# RGBNDR.net
KiCad netlist of a schematic drawn in EAGLE
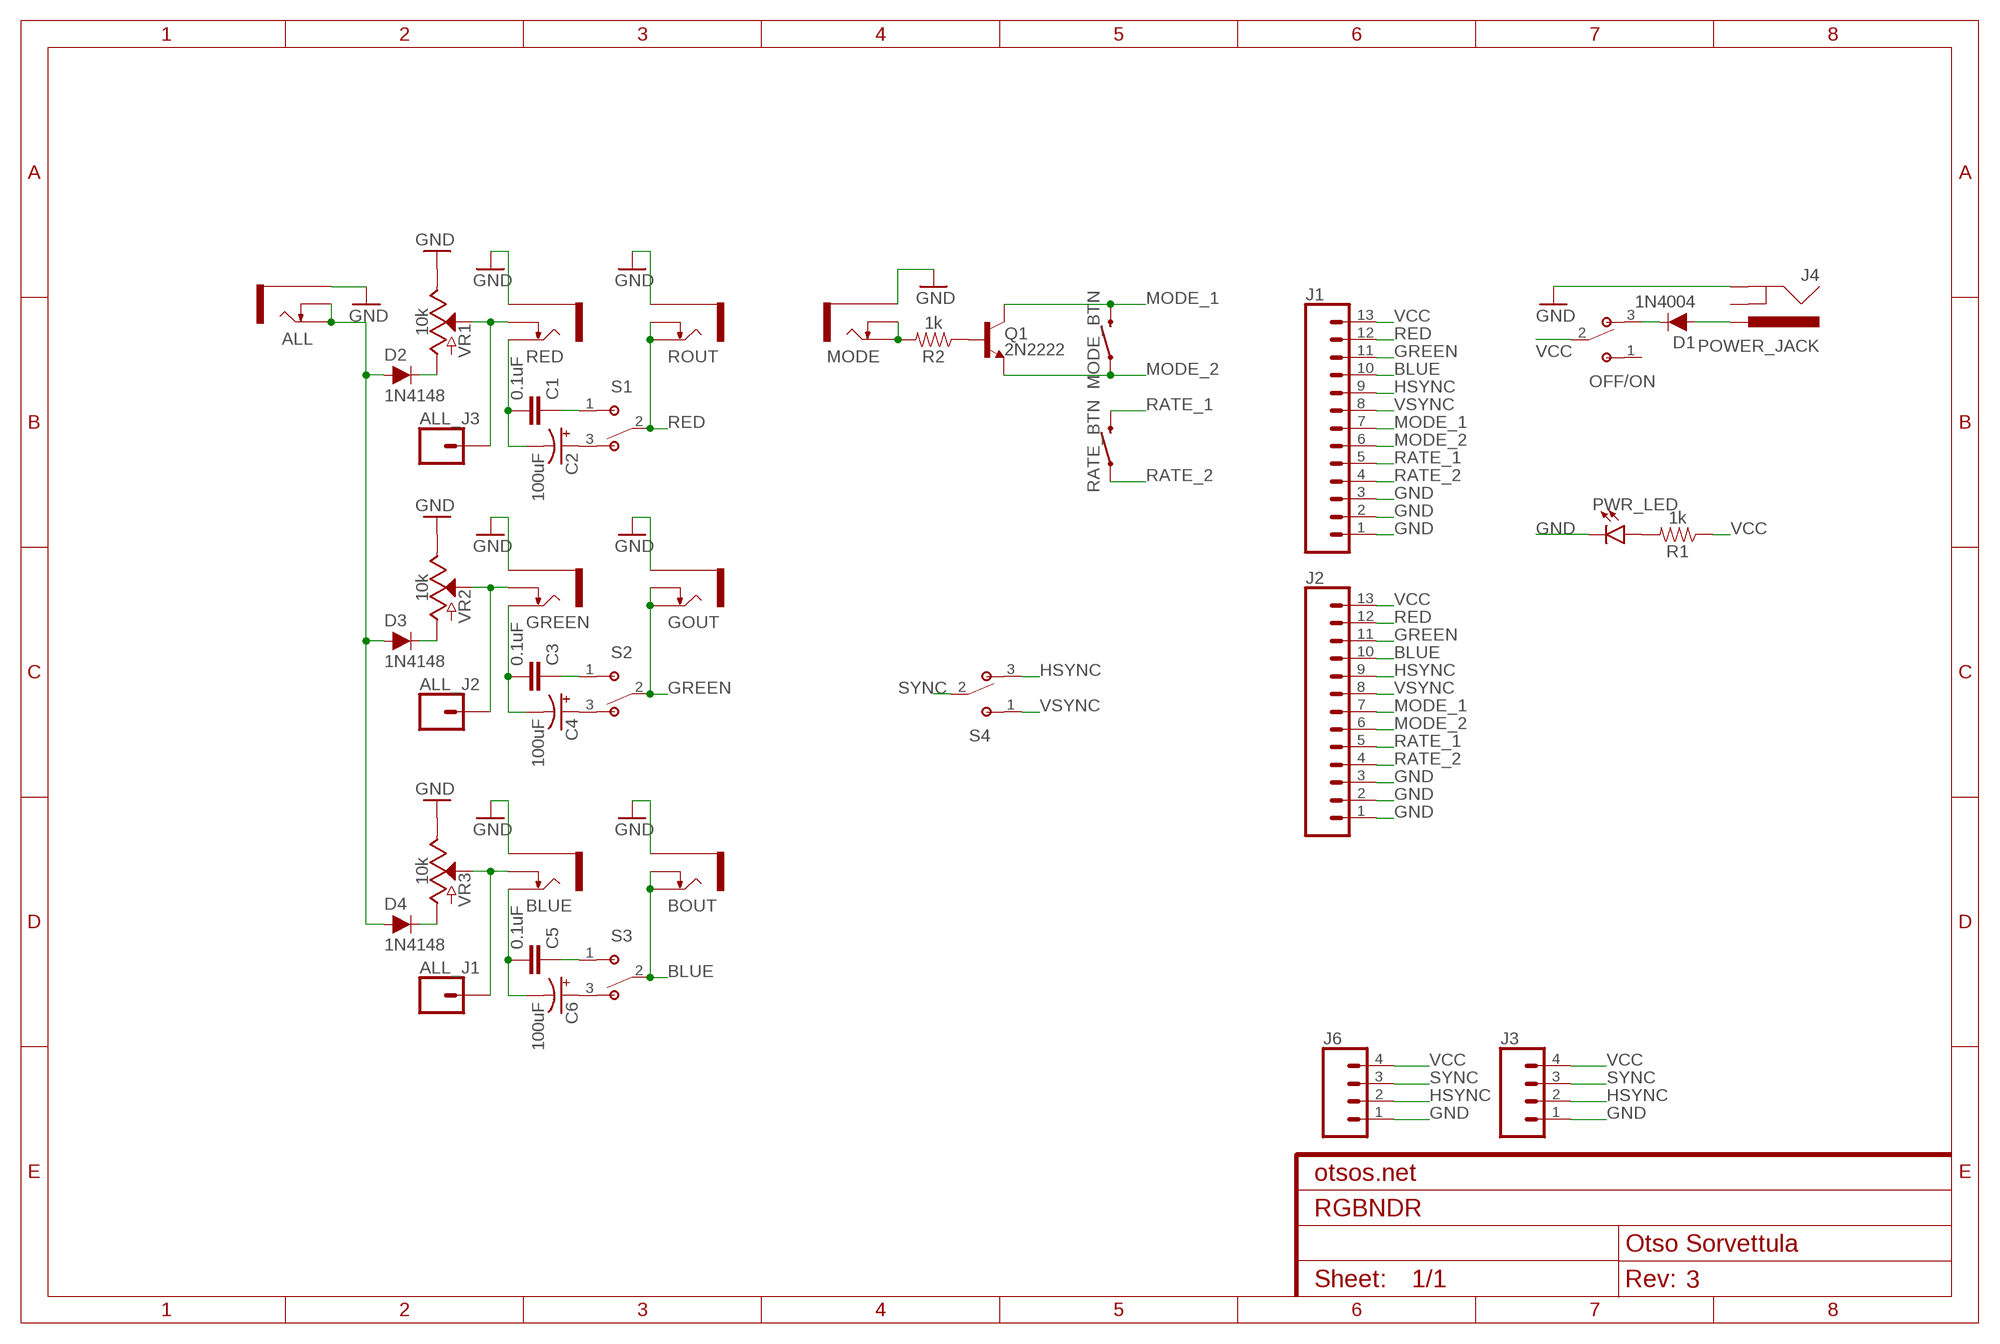
[diagram p0: schematic, sheet 1]

(export (version "E")
  (design (tool "Eeschema 10.0.6"))
  (components
    (comp (ref "ALL")
      (value "THONKICONNNEW")
      (footprint "eagle-import:WQP-PJ301M-12_JACK")
      (libsource (lib "eagle-import") (part "THONKICONNNEW"))
    )
    (comp (ref "ALL_J1")
      (value "CONN_01PTH_NO_SILK_YES_STOP")
      (footprint "eagle-import:1X01_NO_SILK")
      (libsource (lib "eagle-import") (part "CONN_01PTH_NO_SILK_YES_STOP"))
    )
    (comp (ref "ALL_J2")
      (value "CONN_01PTH_NO_SILK_YES_STOP")
      (footprint "eagle-import:1X01_NO_SILK")
      (libsource (lib "eagle-import") (part "CONN_01PTH_NO_SILK_YES_STOP"))
    )
    (comp (ref "ALL_J3")
      (value "CONN_01PTH_NO_SILK_YES_STOP")
      (footprint "eagle-import:1X01_NO_SILK")
      (libsource (lib "eagle-import") (part "CONN_01PTH_NO_SILK_YES_STOP"))
    )
    (comp (ref "BLUE")
      (value "THONKICONNNEW")
      (footprint "eagle-import:WQP-PJ301M-12_JACK")
      (libsource (lib "eagle-import") (part "THONKICONNNEW"))
    )
    (comp (ref "BOUT")
      (value "THONKICONNNEW")
      (footprint "eagle-import:WQP-PJ301M-12_JACK")
      (libsource (lib "eagle-import") (part "THONKICONNNEW"))
    )
    (comp (ref "C1")
      (value "0.1uF")
      (footprint "eagle-import:C025-025X050")
      (libsource (lib "eagle-import") (part "C-EU025-025X050"))
    )
    (comp (ref "C2")
      (value "100uF")
      (footprint "eagle-import:CPOL-RADIAL-2.5MM-6.5MM")
      (libsource (lib "eagle-import") (part "100UF-POLAR-RADIAL-2.5MM-25V-20%"))
    )
    (comp (ref "C3")
      (value "0.1uF")
      (footprint "eagle-import:C025-025X050")
      (libsource (lib "eagle-import") (part "C-EU025-025X050"))
    )
    (comp (ref "C4")
      (value "100uF")
      (footprint "eagle-import:CPOL-RADIAL-2.5MM-6.5MM")
      (libsource (lib "eagle-import") (part "100UF-POLAR-RADIAL-2.5MM-25V-20%"))
    )
    (comp (ref "C5")
      (value "0.1uF")
      (footprint "eagle-import:C025-025X050")
      (libsource (lib "eagle-import") (part "C-EU025-025X050"))
    )
    (comp (ref "C6")
      (value "100uF")
      (footprint "eagle-import:CPOL-RADIAL-2.5MM-6.5MM")
      (libsource (lib "eagle-import") (part "100UF-POLAR-RADIAL-2.5MM-25V-20%"))
    )
    (comp (ref "D1")
      (value "1N4004")
      (footprint "eagle-import:DIODE-1N4001")
      (libsource (lib "eagle-import") (part "DIODE-PTH"))
    )
    (comp (ref "D2")
      (value "1N4148")
      (footprint "eagle-import:DIODE-1N4148")
      (libsource (lib "eagle-import") (part "DIODE-1N4148"))
    )
    (comp (ref "D3")
      (value "1N4148")
      (footprint "eagle-import:DIODE-1N4148")
      (libsource (lib "eagle-import") (part "DIODE-1N4148"))
    )
    (comp (ref "D4")
      (value "1N4148")
      (footprint "eagle-import:DIODE-1N4148")
      (libsource (lib "eagle-import") (part "DIODE-1N4148"))
    )
    (comp (ref "GOUT")
      (value "THONKICONNNEW")
      (footprint "eagle-import:WQP-PJ301M-12_JACK")
      (libsource (lib "eagle-import") (part "THONKICONNNEW"))
    )
    (comp (ref "GREEN")
      (value "THONKICONNNEW")
      (footprint "eagle-import:WQP-PJ301M-12_JACK")
      (libsource (lib "eagle-import") (part "THONKICONNNEW"))
    )
    (comp (ref "J1")
      (value "CONN_13LONGPADS")
      (footprint "eagle-import:1X13-LONGPADS")
      (libsource (lib "eagle-import") (part "CONN_13LONGPADS"))
    )
    (comp (ref "J2")
      (value "CONN_13LONGPADS")
      (footprint "eagle-import:1X13-LONGPADS")
      (libsource (lib "eagle-import") (part "CONN_13LONGPADS"))
    )
    (comp (ref "J3")
      (value "CONN_04")
      (footprint "eagle-import:1X04")
      (libsource (lib "eagle-import") (part "CONN_04"))
    )
    (comp (ref "J4")
      (value "POWER_JACK")
      (footprint "eagle-import:POWER_JACK_PTH")
      (libsource (lib "eagle-import") (part "POWER_JACK"))
    )
    (comp (ref "J6")
      (value "CONN_04")
      (footprint "eagle-import:1X04")
      (libsource (lib "eagle-import") (part "CONN_04"))
    )
    (comp (ref "MODE")
      (value "THONKICONNNEW")
      (footprint "eagle-import:WQP-PJ301M-12_JACK")
      (libsource (lib "eagle-import") (part "THONKICONNNEW"))
    )
    (comp (ref "MODE_BTN")
      (value "MOMENTARY-SWITCH-SPST-PTH-6.0MM")
      (footprint "eagle-import:TACTILE_SWITCH_PTH_6.0MM")
      (libsource (lib "eagle-import") (part "MOMENTARY-SWITCH-SPST-PTH-6.0MM"))
    )
    (comp (ref "OFF/ON")
      (value "OS102011MS2QN1")
      (footprint "eagle-import:SW_OS102011MS2QN1")
      (fields (field (name "MF") "C&K"))
      (libsource (lib "eagle-import") (part "OS102011MS2QN1"))
    )
    (comp (ref "PWR_LED")
      (value "LED3MM")
      (footprint "eagle-import:LED_3MM")
      (libsource (lib "eagle-import") (part "LED3MM"))
    )
    (comp (ref "Q1")
      (value "2N2222")
      (footprint "eagle-import:TO-92")
      (libsource (lib "eagle-import") (part "TRANS_NPN-2N3904"))
    )
    (comp (ref "R1")
      (value "1k")
      (footprint "eagle-import:AXIAL-0.3")
      (libsource (lib "eagle-import") (part "1KOHM-HORIZ-1/4W-1%"))
    )
    (comp (ref "R2")
      (value "1k")
      (footprint "eagle-import:AXIAL-0.3")
      (libsource (lib "eagle-import") (part "1KOHM-HORIZ-1/4W-1%"))
    )
    (comp (ref "RATE_BTN")
      (value "MOMENTARY-SWITCH-SPST-PTH-6.0MM")
      (footprint "eagle-import:TACTILE_SWITCH_PTH_6.0MM")
      (libsource (lib "eagle-import") (part "MOMENTARY-SWITCH-SPST-PTH-6.0MM"))
    )
    (comp (ref "RED")
      (value "THONKICONNNEW")
      (footprint "eagle-import:WQP-PJ301M-12_JACK")
      (libsource (lib "eagle-import") (part "THONKICONNNEW"))
    )
    (comp (ref "ROUT")
      (value "THONKICONNNEW")
      (footprint "eagle-import:WQP-PJ301M-12_JACK")
      (libsource (lib "eagle-import") (part "THONKICONNNEW"))
    )
    (comp (ref "S1")
      (value "OS102011MS2QN1")
      (footprint "eagle-import:SW_OS102011MS2QN1")
      (fields (field (name "MF") "C&K"))
      (libsource (lib "eagle-import") (part "OS102011MS2QN1"))
    )
    (comp (ref "S2")
      (value "OS102011MS2QN1")
      (footprint "eagle-import:SW_OS102011MS2QN1")
      (fields (field (name "MF") "C&K"))
      (libsource (lib "eagle-import") (part "OS102011MS2QN1"))
    )
    (comp (ref "S3")
      (value "OS102011MS2QN1")
      (footprint "eagle-import:SW_OS102011MS2QN1")
      (fields (field (name "MF") "C&K"))
      (libsource (lib "eagle-import") (part "OS102011MS2QN1"))
    )
    (comp (ref "S4")
      (value "OS102011MS2QN1")
      (footprint "eagle-import:SW_OS102011MS2QN1")
      (fields (field (name "MF") "C&K"))
      (libsource (lib "eagle-import") (part "OS102011MS2QN1"))
    )
    (comp (ref "VR1")
      (value "10k")
      (footprint "eagle-import:POT-PTH-ALPS")
      (libsource (lib "eagle-import") (part "POTENTIOMETER-PTH-9MM-1/20W-20%"))
    )
    (comp (ref "VR2")
      (value "10k")
      (footprint "eagle-import:POT-PTH-ALPS")
      (libsource (lib "eagle-import") (part "POTENTIOMETER-PTH-9MM-1/20W-20%"))
    )
    (comp (ref "VR3")
      (value "10k")
      (footprint "eagle-import:POT-PTH-ALPS")
      (libsource (lib "eagle-import") (part "POTENTIOMETER-PTH-9MM-1/20W-20%"))
    )
  )
  (nets
    (net (code "1") (name "/BLUE") (class "Default")
      (node (ref "BOUT") (pin "P$1_TIP") (pinfunction "TIP_P$1_TIP") (pintype "passive"))
      (node (ref "BOUT") (pin "P$2_SWITCH") (pinfunction "SWITCH_P$2_SWITCH") (pintype "passive"))
      (node (ref "J1") (pin "10") (pinfunction "10_10") (pintype "passive"))
      (node (ref "J2") (pin "10") (pinfunction "10_10") (pintype "passive"))
      (node (ref "S3") (pin "2") (pinfunction "2_2") (pintype "passive"))
    )
    (net (code "2") (name "/GREEN") (class "Default")
      (node (ref "GOUT") (pin "P$1_TIP") (pinfunction "TIP_P$1_TIP") (pintype "passive"))
      (node (ref "GOUT") (pin "P$2_SWITCH") (pinfunction "SWITCH_P$2_SWITCH") (pintype "passive"))
      (node (ref "J1") (pin "11") (pinfunction "11_11") (pintype "passive"))
      (node (ref "J2") (pin "11") (pinfunction "11_11") (pintype "passive"))
      (node (ref "S2") (pin "2") (pinfunction "2_2") (pintype "passive"))
    )
    (net (code "3") (name "/HSYNC") (class "Default")
      (node (ref "J1") (pin "9") (pinfunction "9_9") (pintype "passive"))
      (node (ref "J2") (pin "9") (pinfunction "9_9") (pintype "passive"))
      (node (ref "J3") (pin "2") (pinfunction "2_2") (pintype "passive"))
      (node (ref "J6") (pin "2") (pinfunction "2_2") (pintype "passive"))
      (node (ref "S4") (pin "3") (pinfunction "3_3") (pintype "passive"))
    )
    (net (code "4") (name "/MODE_1") (class "Default")
      (node (ref "J1") (pin "7") (pinfunction "7_7") (pintype "passive"))
      (node (ref "J2") (pin "7") (pinfunction "7_7") (pintype "passive"))
      (node (ref "MODE_BTN") (pin "3") (pinfunction "2_3") (pintype "passive"))
      (node (ref "Q1") (pin "3") (pinfunction "C_3") (pintype "passive"))
    )
    (net (code "5") (name "/MODE_2") (class "Default")
      (node (ref "J1") (pin "6") (pinfunction "6_6") (pintype "passive"))
      (node (ref "J2") (pin "6") (pinfunction "6_6") (pintype "passive"))
      (node (ref "MODE_BTN") (pin "1") (pinfunction "1_1") (pintype "passive"))
      (node (ref "Q1") (pin "1") (pinfunction "E_1") (pintype "passive"))
    )
    (net (code "6") (name "/RATE_1") (class "Default")
      (node (ref "J1") (pin "5") (pinfunction "5_5") (pintype "passive"))
      (node (ref "J2") (pin "5") (pinfunction "5_5") (pintype "passive"))
      (node (ref "RATE_BTN") (pin "3") (pinfunction "2_3") (pintype "passive"))
    )
    (net (code "7") (name "/RATE_2") (class "Default")
      (node (ref "J1") (pin "4") (pinfunction "4_4") (pintype "passive"))
      (node (ref "J2") (pin "4") (pinfunction "4_4") (pintype "passive"))
      (node (ref "RATE_BTN") (pin "1") (pinfunction "1_1") (pintype "passive"))
    )
    (net (code "8") (name "/RED") (class "Default")
      (node (ref "J1") (pin "12") (pinfunction "12_12") (pintype "passive"))
      (node (ref "J2") (pin "12") (pinfunction "12_12") (pintype "passive"))
      (node (ref "ROUT") (pin "P$1_TIP") (pinfunction "TIP_P$1_TIP") (pintype "passive"))
      (node (ref "ROUT") (pin "P$2_SWITCH") (pinfunction "SWITCH_P$2_SWITCH") (pintype "passive"))
      (node (ref "S1") (pin "2") (pinfunction "2_2") (pintype "passive"))
    )
    (net (code "9") (name "/SYNC") (class "Default")
      (node (ref "J3") (pin "3") (pinfunction "3_3") (pintype "passive"))
      (node (ref "J6") (pin "3") (pinfunction "3_3") (pintype "passive"))
      (node (ref "S4") (pin "2") (pinfunction "2_2") (pintype "passive"))
    )
    (net (code "10") (name "/VCC") (class "Default")
      (node (ref "J1") (pin "13") (pinfunction "13_13") (pintype "passive"))
      (node (ref "J2") (pin "13") (pinfunction "13_13") (pintype "passive"))
      (node (ref "J3") (pin "4") (pinfunction "4_4") (pintype "passive"))
      (node (ref "J6") (pin "4") (pinfunction "4_4") (pintype "passive"))
      (node (ref "OFF/ON") (pin "2") (pinfunction "2_2") (pintype "passive"))
      (node (ref "R1") (pin "P$1") (pinfunction "1_P$1") (pintype "passive"))
    )
    (net (code "11") (name "/VSYNC") (class "Default")
      (node (ref "J1") (pin "8") (pinfunction "8_8") (pintype "passive"))
      (node (ref "J2") (pin "8") (pinfunction "8_8") (pintype "passive"))
      (node (ref "S4") (pin "1") (pinfunction "1_1") (pintype "passive"))
    )
    (net (code "12") (name "GND") (class "Default")
      (node (ref "ALL") (pin "P$3_SLEEVE") (pinfunction "SLEEVE_P$3_SLEEVE") (pintype "passive"))
      (node (ref "BLUE") (pin "P$3_SLEEVE") (pinfunction "SLEEVE_P$3_SLEEVE") (pintype "passive"))
      (node (ref "BOUT") (pin "P$3_SLEEVE") (pinfunction "SLEEVE_P$3_SLEEVE") (pintype "passive"))
      (node (ref "GOUT") (pin "P$3_SLEEVE") (pinfunction "SLEEVE_P$3_SLEEVE") (pintype "passive"))
      (node (ref "GREEN") (pin "P$3_SLEEVE") (pinfunction "SLEEVE_P$3_SLEEVE") (pintype "passive"))
      (node (ref "J1") (pin "1") (pinfunction "1_1") (pintype "passive"))
      (node (ref "J1") (pin "2") (pinfunction "2_2") (pintype "passive"))
      (node (ref "J1") (pin "3") (pinfunction "3_3") (pintype "passive"))
      (node (ref "J2") (pin "1") (pinfunction "1_1") (pintype "passive"))
      (node (ref "J2") (pin "2") (pinfunction "2_2") (pintype "passive"))
      (node (ref "J2") (pin "3") (pinfunction "3_3") (pintype "passive"))
      (node (ref "J3") (pin "1") (pinfunction "1_1") (pintype "passive"))
      (node (ref "J4") (pin "GND") (pinfunction "GND_GND") (pintype "bidirectional"))
      (node (ref "J6") (pin "1") (pinfunction "1_1") (pintype "passive"))
      (node (ref "MODE") (pin "P$3_SLEEVE") (pinfunction "SLEEVE_P$3_SLEEVE") (pintype "passive"))
      (node (ref "PWR_LED") (pin "K") (pinfunction "C_K") (pintype "passive"))
      (node (ref "RED") (pin "P$3_SLEEVE") (pinfunction "SLEEVE_P$3_SLEEVE") (pintype "passive"))
      (node (ref "ROUT") (pin "P$3_SLEEVE") (pinfunction "SLEEVE_P$3_SLEEVE") (pintype "passive"))
      (node (ref "VR1") (pin "P$1") (pinfunction "E_P$1") (pintype "passive"))
      (node (ref "VR2") (pin "P$1") (pinfunction "E_P$1") (pintype "passive"))
      (node (ref "VR3") (pin "P$1") (pinfunction "E_P$1") (pintype "passive"))
    )
    (net (code "13") (name "Net-(ALL-SWITCH)") (class "Default")
      (node (ref "ALL") (pin "P$1_TIP") (pinfunction "TIP_P$1_TIP") (pintype "passive"))
      (node (ref "ALL") (pin "P$2_SWITCH") (pinfunction "SWITCH_P$2_SWITCH") (pintype "passive"))
      (node (ref "D2") (pin "A") (pinfunction "A_A") (pintype "passive"))
      (node (ref "D3") (pin "A") (pinfunction "A_A") (pintype "passive"))
      (node (ref "D4") (pin "A") (pinfunction "A_A") (pintype "passive"))
    )
    (net (code "14") (name "Net-(BLUE-SWITCH)") (class "Default")
      (node (ref "ALL_J1") (pin "1") (pinfunction "1_1") (pintype "passive"))
      (node (ref "BLUE") (pin "P$2_SWITCH") (pinfunction "SWITCH_P$2_SWITCH") (pintype "passive"))
      (node (ref "VR3") (pin "P$2") (pinfunction "S_P$2") (pintype "passive"))
    )
    (net (code "15") (name "Net-(BLUE-TIP)") (class "Default")
      (node (ref "BLUE") (pin "P$1_TIP") (pinfunction "TIP_P$1_TIP") (pintype "passive"))
      (node (ref "C5") (pin "2") (pinfunction "2_2") (pintype "passive"))
      (node (ref "C6") (pin "2") (pinfunction "-_2") (pintype "passive"))
    )
    (net (code "16") (name "Net-(C1-Pad1)") (class "Default")
      (node (ref "C1") (pin "1") (pinfunction "1_1") (pintype "passive"))
      (node (ref "S1") (pin "1") (pinfunction "1_1") (pintype "passive"))
    )
    (net (code "17") (name "Net-(C2-+)") (class "Default")
      (node (ref "C2") (pin "1") (pinfunction "+_1") (pintype "passive"))
      (node (ref "S1") (pin "3") (pinfunction "3_3") (pintype "passive"))
    )
    (net (code "18") (name "Net-(C2--)") (class "Default")
      (node (ref "C1") (pin "2") (pinfunction "2_2") (pintype "passive"))
      (node (ref "C2") (pin "2") (pinfunction "-_2") (pintype "passive"))
      (node (ref "RED") (pin "P$1_TIP") (pinfunction "TIP_P$1_TIP") (pintype "passive"))
    )
    (net (code "19") (name "Net-(C3-Pad1)") (class "Default")
      (node (ref "C3") (pin "1") (pinfunction "1_1") (pintype "passive"))
      (node (ref "S2") (pin "1") (pinfunction "1_1") (pintype "passive"))
    )
    (net (code "20") (name "Net-(C4-+)") (class "Default")
      (node (ref "C4") (pin "1") (pinfunction "+_1") (pintype "passive"))
      (node (ref "S2") (pin "3") (pinfunction "3_3") (pintype "passive"))
    )
    (net (code "21") (name "Net-(C4--)") (class "Default")
      (node (ref "C3") (pin "2") (pinfunction "2_2") (pintype "passive"))
      (node (ref "C4") (pin "2") (pinfunction "-_2") (pintype "passive"))
      (node (ref "GREEN") (pin "P$1_TIP") (pinfunction "TIP_P$1_TIP") (pintype "passive"))
    )
    (net (code "22") (name "Net-(C5-Pad1)") (class "Default")
      (node (ref "C5") (pin "1") (pinfunction "1_1") (pintype "passive"))
      (node (ref "S3") (pin "1") (pinfunction "1_1") (pintype "passive"))
    )
    (net (code "23") (name "Net-(C6-+)") (class "Default")
      (node (ref "C6") (pin "1") (pinfunction "+_1") (pintype "passive"))
      (node (ref "S3") (pin "3") (pinfunction "3_3") (pintype "passive"))
    )
    (net (code "24") (name "Net-(D1-PadA)") (class "Default")
      (node (ref "D1") (pin "A") (pinfunction "A_A") (pintype "passive"))
      (node (ref "J4") (pin "PWR") (pinfunction "PWR_PWR") (pintype "bidirectional"))
    )
    (net (code "25") (name "Net-(D1-PadC)") (class "Default")
      (node (ref "D1") (pin "C") (pinfunction "C_C") (pintype "passive"))
      (node (ref "OFF/ON") (pin "3") (pinfunction "3_3") (pintype "passive"))
    )
    (net (code "26") (name "Net-(GREEN-SWITCH)") (class "Default")
      (node (ref "ALL_J2") (pin "1") (pinfunction "1_1") (pintype "passive"))
      (node (ref "GREEN") (pin "P$2_SWITCH") (pinfunction "SWITCH_P$2_SWITCH") (pintype "passive"))
      (node (ref "VR2") (pin "P$2") (pinfunction "S_P$2") (pintype "passive"))
    )
    (net (code "27") (name "Net-(MODE-SWITCH)") (class "Default")
      (node (ref "MODE") (pin "P$1_TIP") (pinfunction "TIP_P$1_TIP") (pintype "passive"))
      (node (ref "MODE") (pin "P$2_SWITCH") (pinfunction "SWITCH_P$2_SWITCH") (pintype "passive"))
      (node (ref "R2") (pin "P$2") (pinfunction "2_P$2") (pintype "passive"))
    )
    (net (code "28") (name "Net-(Q1-B)") (class "Default")
      (node (ref "Q1") (pin "2") (pinfunction "B_2") (pintype "passive"))
      (node (ref "R2") (pin "P$1") (pinfunction "1_P$1") (pintype "passive"))
    )
    (net (code "29") (name "Net-(R1-2)") (class "Default")
      (node (ref "PWR_LED") (pin "A") (pinfunction "A_A") (pintype "passive"))
      (node (ref "R1") (pin "P$2") (pinfunction "2_P$2") (pintype "passive"))
    )
    (net (code "30") (name "Net-(RED-SWITCH)") (class "Default")
      (node (ref "ALL_J3") (pin "1") (pinfunction "1_1") (pintype "passive"))
      (node (ref "RED") (pin "P$2_SWITCH") (pinfunction "SWITCH_P$2_SWITCH") (pintype "passive"))
      (node (ref "VR1") (pin "P$2") (pinfunction "S_P$2") (pintype "passive"))
    )
    (net (code "31") (name "Net-(VR1-A)") (class "Default")
      (node (ref "D2") (pin "C") (pinfunction "C_C") (pintype "passive"))
      (node (ref "VR1") (pin "P$3") (pinfunction "A_P$3") (pintype "passive"))
    )
    (net (code "32") (name "Net-(VR2-A)") (class "Default")
      (node (ref "D3") (pin "C") (pinfunction "C_C") (pintype "passive"))
      (node (ref "VR2") (pin "P$3") (pinfunction "A_P$3") (pintype "passive"))
    )
    (net (code "33") (name "Net-(VR3-A)") (class "Default")
      (node (ref "D4") (pin "C") (pinfunction "C_C") (pintype "passive"))
      (node (ref "VR3") (pin "P$3") (pinfunction "A_P$3") (pintype "passive"))
    )
    (net (code "34") (name "unconnected-(J4-PadGNDBREAK)") (class "Default")
      (node (ref "J4") (pin "GNDBREAK") (pinfunction "GNDBREAK_GNDBREAK") (pintype "bidirectional"))
    )
    (net (code "35") (name "unconnected-(OFF/ON-Pad1)") (class "Default")
      (node (ref "OFF/ON") (pin "1") (pinfunction "1_1") (pintype "passive"))
    )
  )
)
